# Bottom_Board.net
KiCad netlist of a schematic drawn in Altium Designer
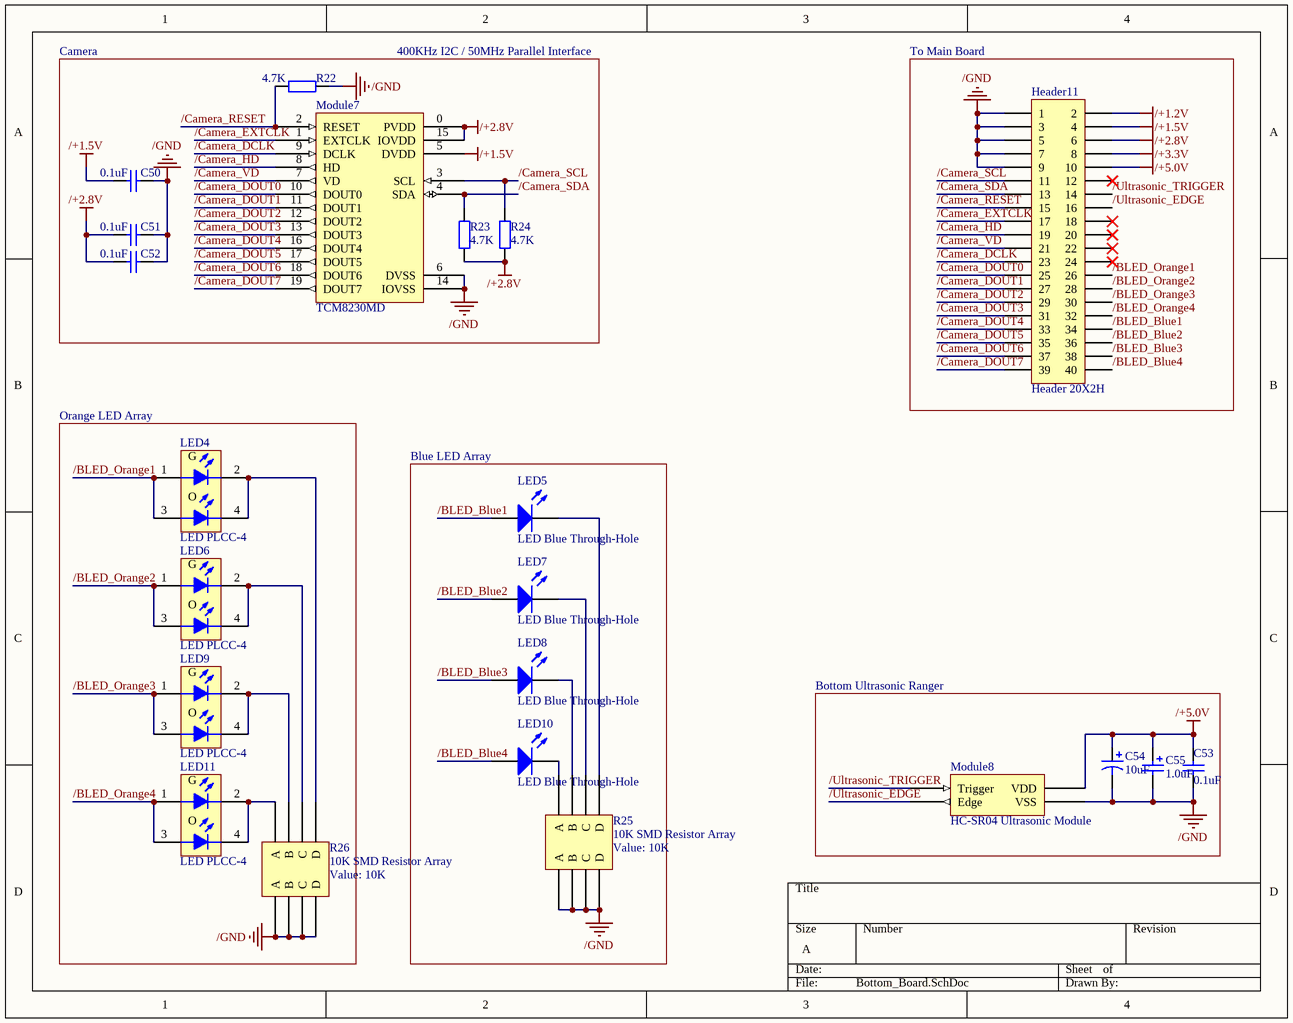
[diagram p0: Bottom_Board.SchDoc]

(export (version "E")
  (design (tool "Eeschema 10.0.6"))
  (components
    (comp (ref "C50")
      (value "0.1uF")
      (footprint "SMD 1206")
      (description "Capacitor")
      (fields (field (name "Comment") "0.1uF SMD 1206"))
      (libsource (lib "Miscellaneous Devices") (part "Cap"))
    )
    (comp (ref "C51")
      (value "0.1uF")
      (footprint "SMD 1206")
      (description "Capacitor")
      (fields (field (name "Comment") "0.1uF SMD 1206"))
      (libsource (lib "Miscellaneous Devices") (part "Cap"))
    )
    (comp (ref "C52")
      (value "0.1uF")
      (footprint "SMD 1206")
      (description "Capacitor")
      (fields (field (name "Comment") "0.1uF SMD 1206"))
      (libsource (lib "Miscellaneous Devices") (part "Cap"))
    )
    (comp (ref "C53")
      (value "0.1uF")
      (footprint "SMD 1206")
      (description "Capacitor")
      (fields (field (name "Comment") "0.1uF SMD 1206"))
      (libsource (lib "Miscellaneous Devices") (part "Cap"))
    )
    (comp (ref "C54")
      (value "10uF")
      (footprint "CAPPR2-5x5")
      (description "Polarized Capacitor (Radial)")
      (fields (field (name "Comment") "10uF Electrolitic") (field (name "PUBLISHER") "Altium Limited"))
      (libsource (lib "Miscellaneous Devices") (part "Cap Pol1"))
    )
    (comp (ref "C55")
      (value "1.0uF")
      (footprint "Capacitor - Tantalum Case A")
      (description "Tantalum Capacitor - Case A")
      (fields (field (name "Comment") "1.0uF Low-ESR Tantalum CaseA"))
      (libsource (lib "Ad-Flier_Parts") (part "SMD_Cap_Tantalum"))
    )
    (comp (ref "Header11")
      (value "Header 20X2H")
      (footprint "HDR2X20H")
      (description "Header, 20-Pin, Dual row, Right Angle")
      (fields (field (name "PUBLISHER") "Altium Limited"))
      (libsource (lib "Miscellaneous Connectors") (part "Header 20X2H"))
    )
    (comp (ref "LED4")
      (value "LED PLCC-4")
      (footprint "PLCC-4 LED")
      (description "Surface Mount Chip LED")
      (fields (field (name "PUBLISHER") "Altium Limited"))
      (libsource (lib "Avago Optoelectronic LED") (part "LED PLCC-4"))
    )
    (comp (ref "LED5")
      (value "LED Blue Through-Hole")
      (footprint "Blue LED")
      (description "Typical INFRARED GaAs LED")
      (fields (field (name "PUBLISHER") "Altium Limited"))
      (libsource (lib "Miscellaneous Devices") (part "LED0"))
    )
    (comp (ref "LED6")
      (value "LED PLCC-4")
      (footprint "PLCC-4 LED")
      (description "Surface Mount Chip LED")
      (fields (field (name "PUBLISHER") "Altium Limited"))
      (libsource (lib "Avago Optoelectronic LED") (part "LED PLCC-4"))
    )
    (comp (ref "LED7")
      (value "LED Blue Through-Hole")
      (footprint "Blue LED")
      (description "Typical INFRARED GaAs LED")
      (fields (field (name "PUBLISHER") "Altium Limited"))
      (libsource (lib "Miscellaneous Devices") (part "LED0"))
    )
    (comp (ref "LED8")
      (value "LED Blue Through-Hole")
      (footprint "Blue LED")
      (description "Typical INFRARED GaAs LED")
      (fields (field (name "PUBLISHER") "Altium Limited"))
      (libsource (lib "Miscellaneous Devices") (part "LED0"))
    )
    (comp (ref "LED9")
      (value "LED PLCC-4")
      (footprint "PLCC-4 LED")
      (description "Surface Mount Chip LED")
      (fields (field (name "PUBLISHER") "Altium Limited"))
      (libsource (lib "Avago Optoelectronic LED") (part "LED PLCC-4"))
    )
    (comp (ref "LED10")
      (value "LED Blue Through-Hole")
      (footprint "Blue LED")
      (description "Typical INFRARED GaAs LED")
      (fields (field (name "PUBLISHER") "Altium Limited"))
      (libsource (lib "Miscellaneous Devices") (part "LED0"))
    )
    (comp (ref "LED11")
      (value "LED PLCC-4")
      (footprint "PLCC-4 LED")
      (description "Surface Mount Chip LED")
      (fields (field (name "PUBLISHER") "Altium Limited"))
      (libsource (lib "Avago Optoelectronic LED") (part "LED PLCC-4"))
    )
    (comp (ref "Module7")
      (value "TCM8230MD")
      (footprint "TCM8230MD Camera Module")
      (description "Toshiba 640x480 Camera")
      (libsource (lib "Ad-Flier_Parts") (part "TCM8230MD"))
    )
    (comp (ref "Module8")
      (value "HC-SR04 Ultrasonic Module")
      (footprint "HC-SR04 Ultrasonic Ranger")
      (libsource (lib "Ad-Flier_Parts") (part "HC-SR04 Ultrasonic Module"))
    )
    (comp (ref "R22")
      (value "4.7K")
      (footprint "SMD 0805")
      (description "Resistor")
      (fields (field (name "Comment") "4.7K SMD 0805"))
      (libsource (lib "") (part "Res2_1"))
    )
    (comp (ref "R23")
      (value "4.7K")
      (footprint "SMD 0805")
      (description "Resistor")
      (fields (field (name "Comment") "4.7K SMD 0805"))
      (libsource (lib "Miscellaneous Devices") (part "Res2"))
    )
    (comp (ref "R24")
      (value "4.7K")
      (footprint "SMD 0805")
      (description "Resistor")
      (fields (field (name "Comment") "4.7K SMD 0805"))
      (libsource (lib "") (part "Res2_2"))
    )
    (comp (ref "R25")
      (value "10K SMD Resistor Array")
      (footprint "Resistor Array YC164")
      (description "4-Count Resistor Array")
      (fields (field (name "ALTIUM_VALUE") "10K"))
      (libsource (lib "Ad-Flier_Parts") (part "SMD Resistor Array"))
    )
    (comp (ref "R26")
      (value "10K SMD Resistor Array")
      (footprint "Resistor Array YC164")
      (description "4-Count Resistor Array")
      (fields (field (name "ALTIUM_VALUE") "10K"))
      (libsource (lib "Ad-Flier_Parts") (part "SMD Resistor Array"))
    )
  )
  (nets
    (net (code "1") (name "/{slash}BLED_Blue1") (class "Default")
      (node (ref "Header11") (pin "34") (pinfunction "34_34") (pintype "passive"))
      (node (ref "LED5") (pin "1") (pinfunction "A_1") (pintype "passive"))
    )
    (net (code "2") (name "/{slash}BLED_Blue2") (class "Default")
      (node (ref "Header11") (pin "36") (pinfunction "36_36") (pintype "passive"))
      (node (ref "LED7") (pin "1") (pinfunction "A_1") (pintype "passive"))
    )
    (net (code "3") (name "/{slash}BLED_Blue3") (class "Default")
      (node (ref "Header11") (pin "38") (pinfunction "38_38") (pintype "passive"))
      (node (ref "LED8") (pin "1") (pinfunction "A_1") (pintype "passive"))
    )
    (net (code "4") (name "/{slash}BLED_Blue4") (class "Default")
      (node (ref "Header11") (pin "40") (pinfunction "40_40") (pintype "passive"))
      (node (ref "LED10") (pin "1") (pinfunction "A_1") (pintype "passive"))
    )
    (net (code "5") (name "/{slash}BLED_Orange1") (class "Default")
      (node (ref "Header11") (pin "26") (pinfunction "26_26") (pintype "passive"))
      (node (ref "LED4") (pin "1") (pinfunction "A1_1") (pintype "passive"))
      (node (ref "LED4") (pin "3") (pinfunction "A2_3") (pintype "passive"))
    )
    (net (code "6") (name "/{slash}BLED_Orange2") (class "Default")
      (node (ref "Header11") (pin "28") (pinfunction "28_28") (pintype "passive"))
      (node (ref "LED6") (pin "1") (pinfunction "A1_1") (pintype "passive"))
      (node (ref "LED6") (pin "3") (pinfunction "A2_3") (pintype "passive"))
    )
    (net (code "7") (name "/{slash}BLED_Orange3") (class "Default")
      (node (ref "Header11") (pin "30") (pinfunction "30_30") (pintype "passive"))
      (node (ref "LED9") (pin "1") (pinfunction "A1_1") (pintype "passive"))
      (node (ref "LED9") (pin "3") (pinfunction "A2_3") (pintype "passive"))
    )
    (net (code "8") (name "/{slash}BLED_Orange4") (class "Default")
      (node (ref "Header11") (pin "32") (pinfunction "32_32") (pintype "passive"))
      (node (ref "LED11") (pin "1") (pinfunction "A1_1") (pintype "passive"))
      (node (ref "LED11") (pin "3") (pinfunction "A2_3") (pintype "passive"))
    )
    (net (code "9") (name "/{slash}Camera_DCLK") (class "Default")
      (node (ref "Header11") (pin "23") (pinfunction "23_23") (pintype "passive"))
      (node (ref "Module7") (pin "9") (pinfunction "DCLK_9") (pintype "input"))
    )
    (net (code "10") (name "/{slash}Camera_DOUT0") (class "Default")
      (node (ref "Header11") (pin "25") (pinfunction "25_25") (pintype "passive"))
      (node (ref "Module7") (pin "10") (pinfunction "DOUT0_10") (pintype "output"))
    )
    (net (code "11") (name "/{slash}Camera_DOUT1") (class "Default")
      (node (ref "Header11") (pin "27") (pinfunction "27_27") (pintype "passive"))
      (node (ref "Module7") (pin "11") (pinfunction "DOUT1_11") (pintype "output"))
    )
    (net (code "12") (name "/{slash}Camera_DOUT2") (class "Default")
      (node (ref "Header11") (pin "29") (pinfunction "29_29") (pintype "passive"))
      (node (ref "Module7") (pin "12") (pinfunction "DOUT2_12") (pintype "output"))
    )
    (net (code "13") (name "/{slash}Camera_DOUT3") (class "Default")
      (node (ref "Header11") (pin "31") (pinfunction "31_31") (pintype "passive"))
      (node (ref "Module7") (pin "13") (pinfunction "DOUT3_13") (pintype "output"))
    )
    (net (code "14") (name "/{slash}Camera_DOUT4") (class "Default")
      (node (ref "Header11") (pin "33") (pinfunction "33_33") (pintype "passive"))
      (node (ref "Module7") (pin "16") (pinfunction "DOUT4_16") (pintype "output"))
    )
    (net (code "15") (name "/{slash}Camera_DOUT5") (class "Default")
      (node (ref "Header11") (pin "35") (pinfunction "35_35") (pintype "passive"))
      (node (ref "Module7") (pin "17") (pinfunction "DOUT5_17") (pintype "output"))
    )
    (net (code "16") (name "/{slash}Camera_DOUT6") (class "Default")
      (node (ref "Header11") (pin "37") (pinfunction "37_37") (pintype "passive"))
      (node (ref "Module7") (pin "18") (pinfunction "DOUT6_18") (pintype "output"))
    )
    (net (code "17") (name "/{slash}Camera_DOUT7") (class "Default")
      (node (ref "Header11") (pin "39") (pinfunction "39_39") (pintype "passive"))
      (node (ref "Module7") (pin "19") (pinfunction "DOUT7_19") (pintype "output"))
    )
    (net (code "18") (name "/{slash}Camera_EXTCLK") (class "Default")
      (node (ref "Header11") (pin "17") (pinfunction "17_17") (pintype "passive"))
      (node (ref "Module7") (pin "1") (pinfunction "EXTCLK_1") (pintype "input"))
    )
    (net (code "19") (name "/{slash}Camera_HD") (class "Default")
      (node (ref "Header11") (pin "19") (pinfunction "19_19") (pintype "passive"))
      (node (ref "Module7") (pin "8") (pinfunction "HD_8") (pintype "output"))
    )
    (net (code "20") (name "/{slash}Camera_RESET") (class "Default")
      (node (ref "Header11") (pin "15") (pinfunction "15_15") (pintype "passive"))
      (node (ref "Module7") (pin "2") (pinfunction "RESET_2") (pintype "input"))
      (node (ref "R22") (pin "2") (pinfunction "2_2") (pintype "passive"))
    )
    (net (code "21") (name "/{slash}Camera_SCL") (class "Default")
      (node (ref "Header11") (pin "11") (pinfunction "11_11") (pintype "passive"))
      (node (ref "Module7") (pin "3") (pinfunction "SCL_3") (pintype "input"))
      (node (ref "R24") (pin "1") (pinfunction "1_1") (pintype "passive"))
    )
    (net (code "22") (name "/{slash}Camera_SDA") (class "Default")
      (node (ref "Header11") (pin "13") (pinfunction "13_13") (pintype "passive"))
      (node (ref "Module7") (pin "4") (pinfunction "SDA_4") (pintype "bidirectional"))
      (node (ref "R23") (pin "2") (pinfunction "2_2") (pintype "passive"))
    )
    (net (code "23") (name "/{slash}Camera_VD") (class "Default")
      (node (ref "Header11") (pin "21") (pinfunction "21_21") (pintype "passive"))
      (node (ref "Module7") (pin "7") (pinfunction "VD_7") (pintype "output"))
    )
    (net (code "24") (name "/{slash}Ultrasonic_EDGE") (class "Default")
      (node (ref "Header11") (pin "16") (pinfunction "16_16") (pintype "passive"))
      (node (ref "Module8") (pin "2") (pinfunction "Edge_2") (pintype "output"))
    )
    (net (code "25") (name "/{slash}Ultrasonic_TRIGGER") (class "Default")
      (node (ref "Header11") (pin "14") (pinfunction "14_14") (pintype "passive"))
      (node (ref "Module8") (pin "1") (pinfunction "Trigger_1") (pintype "input"))
    )
    (net (code "26") (name "Net-(LED4-K1)") (class "Default")
      (node (ref "LED4") (pin "2") (pinfunction "K1_2") (pintype "passive"))
      (node (ref "LED4") (pin "4") (pinfunction "K2_4") (pintype "passive"))
      (node (ref "R26") (pin "4") (pinfunction "D_4") (pintype "passive"))
    )
    (net (code "27") (name "Net-(LED5-K)") (class "Default")
      (node (ref "LED5") (pin "2") (pinfunction "K_2") (pintype "passive"))
      (node (ref "R25") (pin "4") (pinfunction "D_4") (pintype "passive"))
    )
    (net (code "28") (name "Net-(LED6-K1)") (class "Default")
      (node (ref "LED6") (pin "2") (pinfunction "K1_2") (pintype "passive"))
      (node (ref "LED6") (pin "4") (pinfunction "K2_4") (pintype "passive"))
      (node (ref "R26") (pin "3") (pinfunction "C_3") (pintype "passive"))
    )
    (net (code "29") (name "Net-(LED7-K)") (class "Default")
      (node (ref "LED7") (pin "2") (pinfunction "K_2") (pintype "passive"))
      (node (ref "R25") (pin "3") (pinfunction "C_3") (pintype "passive"))
    )
    (net (code "30") (name "Net-(LED8-K)") (class "Default")
      (node (ref "LED8") (pin "2") (pinfunction "K_2") (pintype "passive"))
      (node (ref "R25") (pin "2") (pinfunction "B_2") (pintype "passive"))
    )
    (net (code "31") (name "Net-(LED9-K1)") (class "Default")
      (node (ref "LED9") (pin "2") (pinfunction "K1_2") (pintype "passive"))
      (node (ref "LED9") (pin "4") (pinfunction "K2_4") (pintype "passive"))
      (node (ref "R26") (pin "2") (pinfunction "B_2") (pintype "passive"))
    )
    (net (code "32") (name "Net-(LED10-K)") (class "Default")
      (node (ref "LED10") (pin "2") (pinfunction "K_2") (pintype "passive"))
      (node (ref "R25") (pin "1") (pinfunction "A_1") (pintype "passive"))
    )
    (net (code "33") (name "Net-(LED11-K1)") (class "Default")
      (node (ref "LED11") (pin "2") (pinfunction "K1_2") (pintype "passive"))
      (node (ref "LED11") (pin "4") (pinfunction "K2_4") (pintype "passive"))
      (node (ref "R26") (pin "1") (pinfunction "A_1") (pintype "passive"))
    )
    (net (code "34") (name "unconnected-(Header11-Pad12)") (class "Default")
      (node (ref "Header11") (pin "12") (pinfunction "12_12") (pintype "passive+no_connect"))
    )
    (net (code "35") (name "unconnected-(Header11-Pad18)") (class "Default")
      (node (ref "Header11") (pin "18") (pinfunction "18_18") (pintype "passive+no_connect"))
    )
    (net (code "36") (name "unconnected-(Header11-Pad20)") (class "Default")
      (node (ref "Header11") (pin "20") (pinfunction "20_20") (pintype "passive+no_connect"))
    )
    (net (code "37") (name "unconnected-(Header11-Pad22)") (class "Default")
      (node (ref "Header11") (pin "22") (pinfunction "22_22") (pintype "passive+no_connect"))
    )
    (net (code "38") (name "unconnected-(Header11-Pad24)") (class "Default")
      (node (ref "Header11") (pin "24") (pinfunction "24_24") (pintype "passive+no_connect"))
    )
    (net (code "39") (name "{slash}+1.2V") (class "Default")
      (node (ref "Header11") (pin "2") (pinfunction "2_2") (pintype "passive"))
    )
    (net (code "40") (name "{slash}+1.5V") (class "Default")
      (node (ref "C50") (pin "1") (pinfunction "1_1") (pintype "passive"))
      (node (ref "Header11") (pin "4") (pinfunction "4_4") (pintype "passive"))
      (node (ref "Module7") (pin "5") (pinfunction "DVDD_5") (pintype "power_in"))
    )
    (net (code "41") (name "{slash}+2.8V") (class "Default")
      (node (ref "C51") (pin "1") (pinfunction "1_1") (pintype "passive"))
      (node (ref "C52") (pin "1") (pinfunction "1_1") (pintype "passive"))
      (node (ref "Header11") (pin "6") (pinfunction "6_6") (pintype "passive"))
      (node (ref "Module7") (pin "0") (pinfunction "PVDD_0") (pintype "power_in"))
      (node (ref "Module7") (pin "15") (pinfunction "IOVDD_15") (pintype "power_in"))
      (node (ref "R23") (pin "1") (pinfunction "1_1") (pintype "passive"))
      (node (ref "R24") (pin "2") (pinfunction "2_2") (pintype "passive"))
    )
    (net (code "42") (name "{slash}+3.3V") (class "Default")
      (node (ref "Header11") (pin "8") (pinfunction "8_8") (pintype "passive"))
    )
    (net (code "43") (name "{slash}+5.0V") (class "Default")
      (node (ref "C53") (pin "2") (pinfunction "2_2") (pintype "passive"))
      (node (ref "C54") (pin "1") (pinfunction "1_1") (pintype "passive"))
      (node (ref "C55") (pin "1") (pinfunction "+_1") (pintype "passive"))
      (node (ref "Header11") (pin "10") (pinfunction "10_10") (pintype "passive"))
      (node (ref "Module8") (pin "0") (pinfunction "VDD_0") (pintype "power_in"))
    )
    (net (code "44") (name "{slash}GND") (class "Default")
      (node (ref "C50") (pin "2") (pinfunction "2_2") (pintype "passive"))
      (node (ref "C51") (pin "2") (pinfunction "2_2") (pintype "passive"))
      (node (ref "C52") (pin "2") (pinfunction "2_2") (pintype "passive"))
      (node (ref "C53") (pin "1") (pinfunction "1_1") (pintype "passive"))
      (node (ref "C54") (pin "2") (pinfunction "2_2") (pintype "passive"))
      (node (ref "C55") (pin "2") (pinfunction "-_2") (pintype "passive"))
      (node (ref "Header11") (pin "1") (pinfunction "1_1") (pintype "passive"))
      (node (ref "Header11") (pin "3") (pinfunction "3_3") (pintype "passive"))
      (node (ref "Header11") (pin "5") (pinfunction "5_5") (pintype "passive"))
      (node (ref "Header11") (pin "7") (pinfunction "7_7") (pintype "passive"))
      (node (ref "Header11") (pin "9") (pinfunction "9_9") (pintype "passive"))
      (node (ref "Module7") (pin "14") (pinfunction "IOVSS_14") (pintype "power_in"))
      (node (ref "Module7") (pin "6") (pinfunction "DVSS_6") (pintype "power_in"))
      (node (ref "Module8") (pin "3") (pinfunction "VSS_3") (pintype "power_in"))
      (node (ref "R22") (pin "1") (pinfunction "1_1") (pintype "passive"))
      (node (ref "R25") (pin "5") (pinfunction "A_5") (pintype "passive"))
      (node (ref "R25") (pin "6") (pinfunction "B_6") (pintype "passive"))
      (node (ref "R25") (pin "7") (pinfunction "C_7") (pintype "passive"))
      (node (ref "R25") (pin "8") (pinfunction "D_8") (pintype "passive"))
      (node (ref "R26") (pin "5") (pinfunction "A_5") (pintype "passive"))
      (node (ref "R26") (pin "6") (pinfunction "B_6") (pintype "passive"))
      (node (ref "R26") (pin "7") (pinfunction "C_7") (pintype "passive"))
      (node (ref "R26") (pin "8") (pinfunction "D_8") (pintype "passive"))
    )
  )
)
